# MSU-avionics.net
KiCad netlist of a schematic drawn in EasyEDA Pro
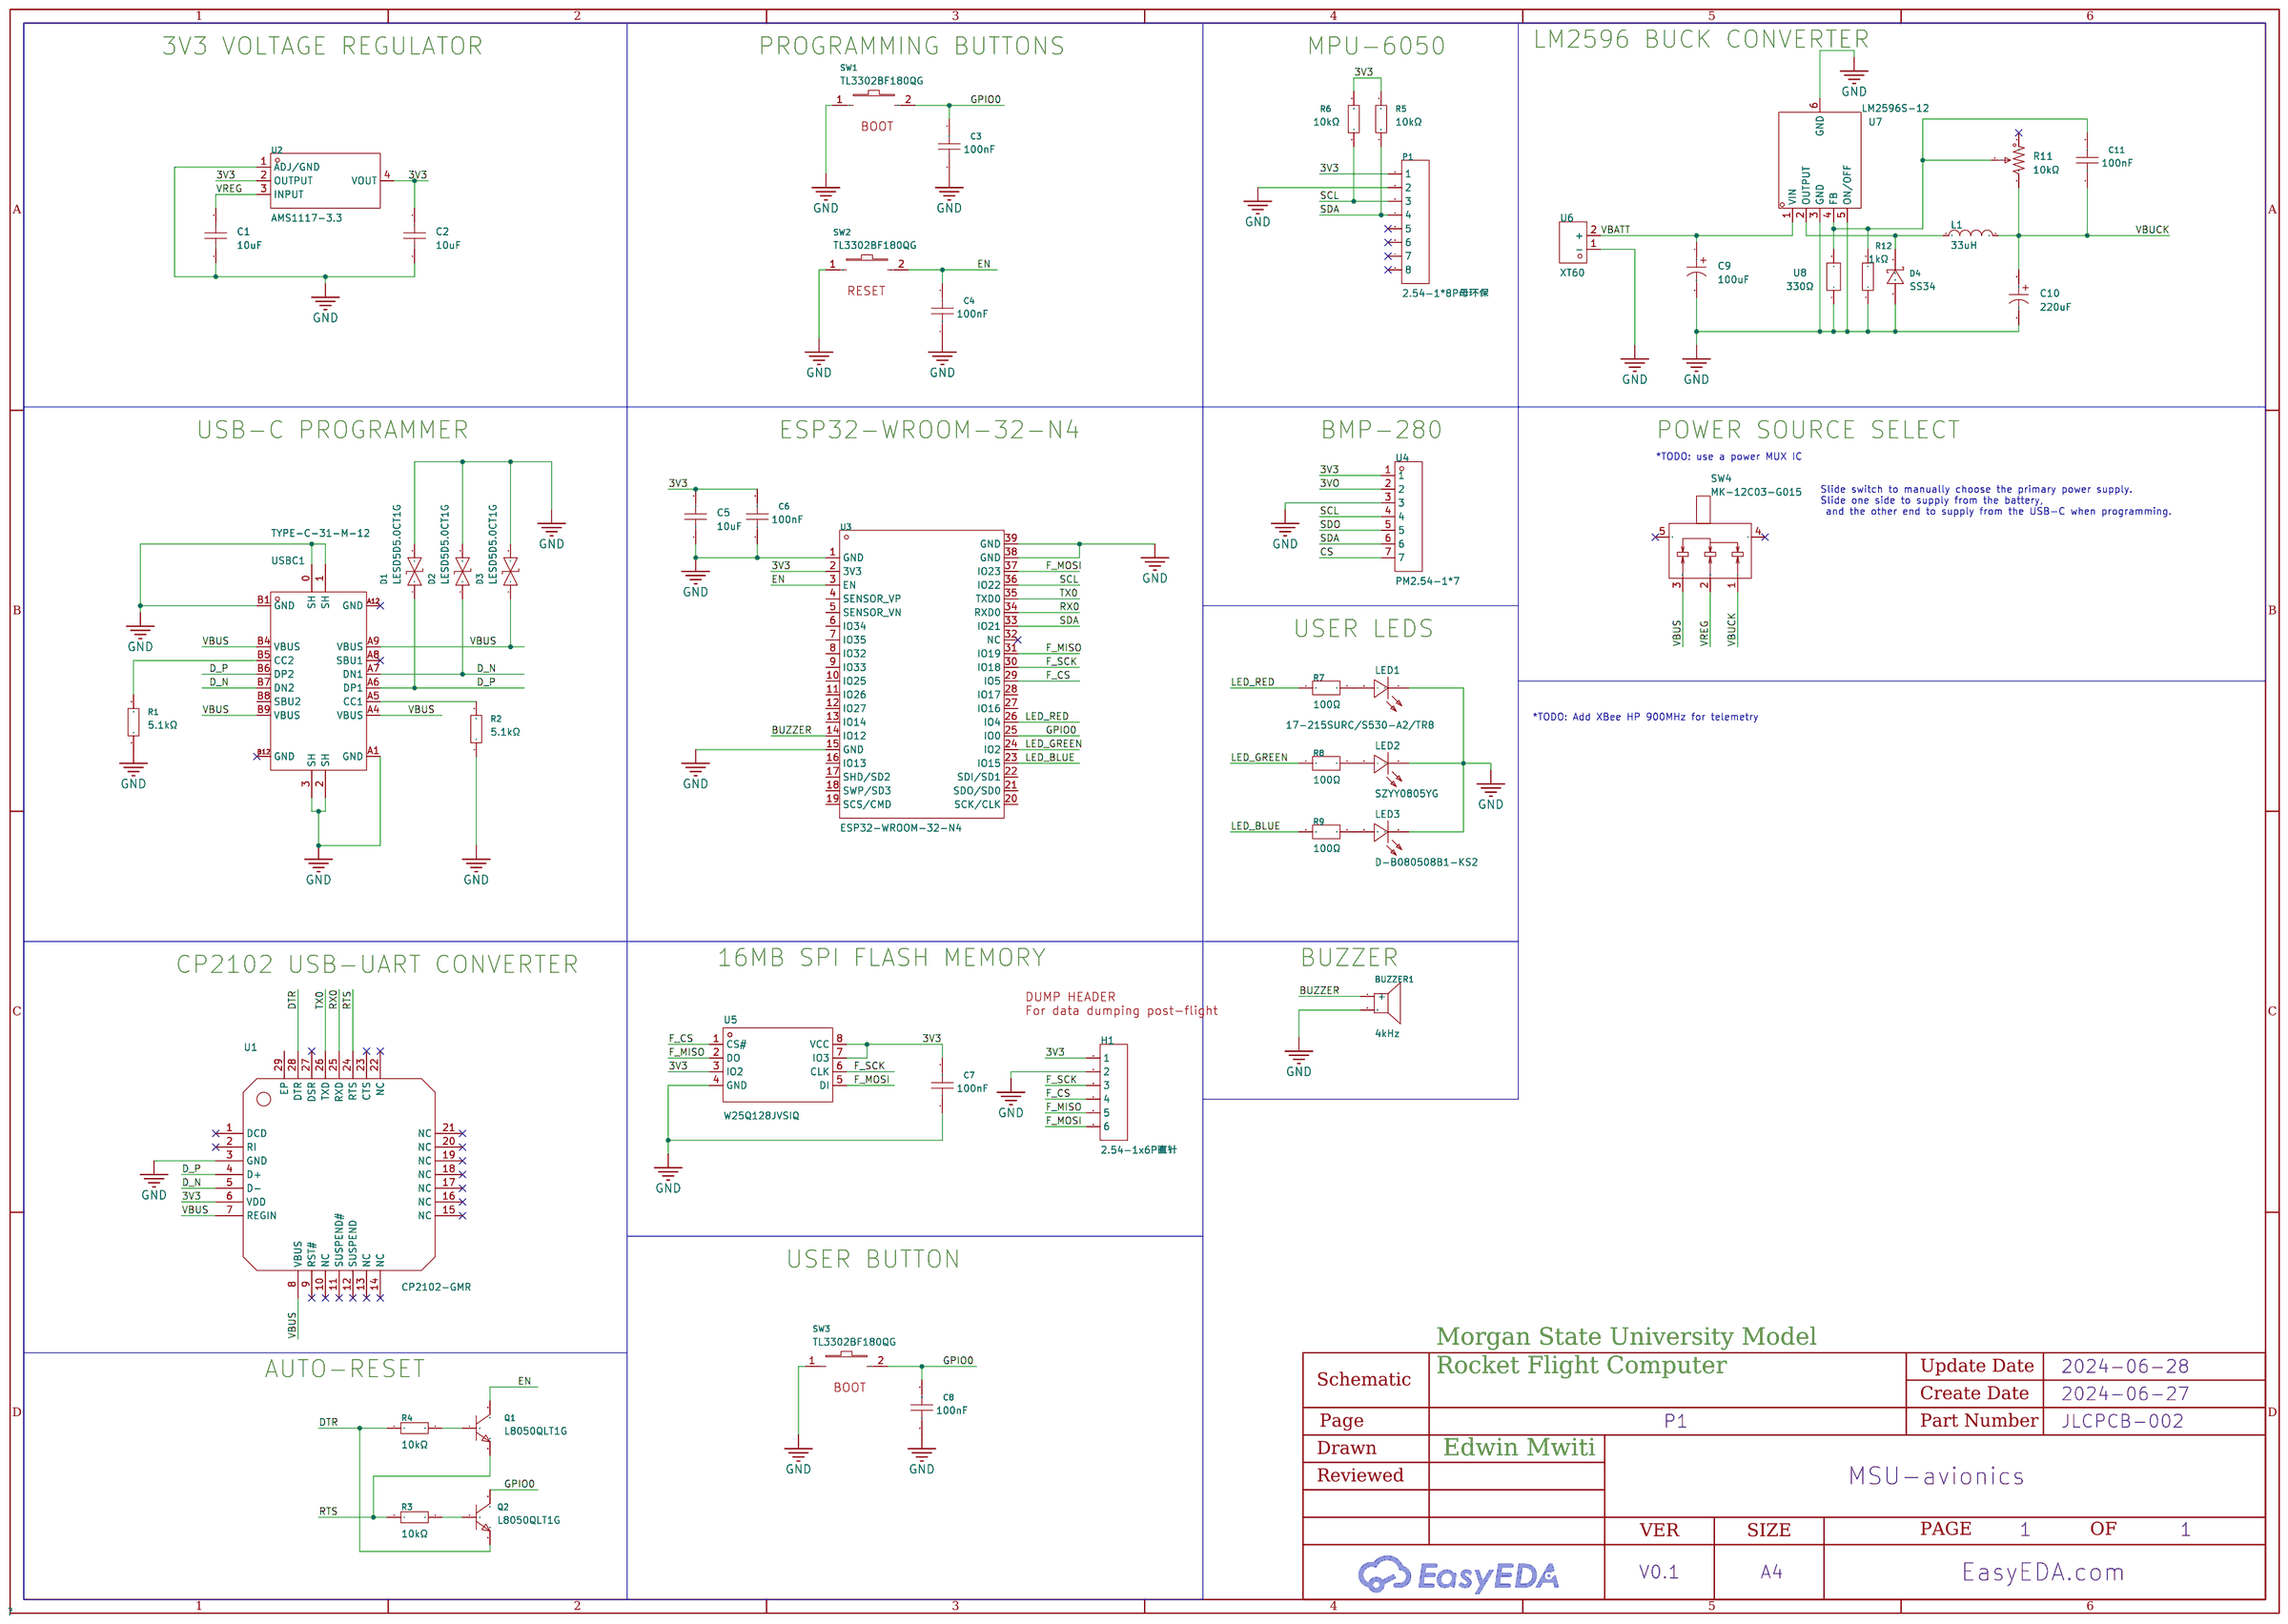
[diagram p0: schematic sheet]

(export (version "E")
  (design (tool "Eeschema 10.0.6"))
  (components
    (comp (ref "BUZZER1")
      (value "4kHz")
      (footprint "easyedapro:BUZ-TH_BD14.0-P5.00-D0.7-FD")
      (fields (field (name "Manufacturer Part") "PS1440P02BT") (field (name "Manufacturer") "TDK"))
      (libsource (lib "easyedapro") (part "PS1440P02BT"))
    )
    (comp (ref "C1")
      (value "10uF")
      (footprint "easyedapro:C0805")
      (fields
        (field (name "Manufacturer Part") "C0805X6S106K250NT")
        (field (name "Manufacturer") "SANYEAR(叁叶源)")
      )
      (libsource (lib "easyedapro") (part "C0805X6S106K250NT"))
    )
    (comp (ref "C2")
      (value "10uF")
      (footprint "easyedapro:C0805")
      (fields
        (field (name "Manufacturer Part") "C0805X6S106K250NT")
        (field (name "Manufacturer") "SANYEAR(叁叶源)")
      )
      (libsource (lib "easyedapro") (part "C0805X6S106K250NT"))
    )
    (comp (ref "C3")
      (value "100nF")
      (footprint "easyedapro:C0805")
      (fields
        (field (name "Manufacturer Part") "CT41G-0805-2X1-50V-0.1μF-K(N)")
        (field (name "Manufacturer") "TORCH(火炬)")
      )
      (libsource (lib "easyedapro") (part "CT41G-0805-2X1-50V-0.1UF-K(N)"))
    )
    (comp (ref "C4")
      (value "100nF")
      (footprint "easyedapro:C0805")
      (fields
        (field (name "Manufacturer Part") "CT41G-0805-2X1-50V-0.1μF-K(N)")
        (field (name "Manufacturer") "TORCH(火炬)")
      )
      (libsource (lib "easyedapro") (part "CT41G-0805-2X1-50V-0.1UF-K(N)"))
    )
    (comp (ref "C5")
      (value "10uF")
      (footprint "easyedapro:C0805")
      (fields
        (field (name "Manufacturer Part") "C0805X6S106K250NT")
        (field (name "Manufacturer") "SANYEAR(叁叶源)")
      )
      (libsource (lib "easyedapro") (part "C0805X6S106K250NT"))
    )
    (comp (ref "C6")
      (value "100nF")
      (footprint "easyedapro:C0805")
      (fields
        (field (name "Manufacturer Part") "CT41G-0805-2X1-50V-0.1μF-K(N)")
        (field (name "Manufacturer") "TORCH(火炬)")
      )
      (libsource (lib "easyedapro") (part "CT41G-0805-2X1-50V-0.1UF-K(N)"))
    )
    (comp (ref "C7")
      (value "100nF")
      (footprint "easyedapro:C0805")
      (fields
        (field (name "Manufacturer Part") "CT41G-0805-2X1-50V-0.1μF-K(N)")
        (field (name "Manufacturer") "TORCH(火炬)")
      )
      (libsource (lib "easyedapro") (part "CT41G-0805-2X1-50V-0.1UF-K(N)"))
    )
    (comp (ref "C8")
      (value "100nF")
      (footprint "easyedapro:C0805")
      (fields
        (field (name "Manufacturer Part") "CT41G-0805-2X1-50V-0.1μF-K(N)")
        (field (name "Manufacturer") "TORCH(火炬)")
      )
      (libsource (lib "easyedapro") (part "CT41G-0805-2X1-50V-0.1UF-K(N)"))
    )
    (comp (ref "C9")
      (value "100uF")
      (footprint "easyedapro:CAP-SMD_BD6.3-L6.6-W6.6-LS7.2-FD")
      (fields
        (field (name "Manufacturer Part") "RX100UF50V90RV0105")
        (field (name "Manufacturer") "KNSCHA(科尼盛)")
      )
      (libsource (lib "easyedapro") (part "RX100UF50V90RV0105"))
    )
    (comp (ref "C10")
      (value "220uF")
      (footprint "easyedapro:CAP-SMD_BD10.0-L10.3-W10.3-FD")
      (fields
        (field (name "Manufacturer Part") "FZ220UF50V90RV0126")
        (field (name "Manufacturer") "KNSCHA(科尼盛)")
      )
      (libsource (lib "easyedapro") (part "FZ220UF50V90RV0126"))
    )
    (comp (ref "C11")
      (value "100nF")
      (footprint "easyedapro:C0805")
      (fields
        (field (name "Manufacturer Part") "CT41G-0805-2X1-50V-0.1μF-K(N)")
        (field (name "Manufacturer") "TORCH(火炬)")
      )
      (libsource (lib "easyedapro") (part "CT41G-0805-2X1-50V-0.1UF-K(N)"))
    )
    (comp (ref "D1")
      (value "LESD5D5.0CT1G")
      (footprint "easyedapro:SOD-523_L1.2-W0.8-LS1.6-BI")
      (fields (field (name "Manufacturer") "LRC(乐山无线电)"))
      (libsource (lib "easyedapro") (part "LESD5D5.0CT1G"))
    )
    (comp (ref "D2")
      (value "LESD5D5.0CT1G")
      (footprint "easyedapro:SOD-523_L1.2-W0.8-LS1.6-BI")
      (fields (field (name "Manufacturer") "LRC(乐山无线电)"))
      (libsource (lib "easyedapro") (part "LESD5D5.0CT1G"))
    )
    (comp (ref "D3")
      (value "LESD5D5.0CT1G")
      (footprint "easyedapro:SOD-523_L1.2-W0.8-LS1.6-BI")
      (fields (field (name "Manufacturer") "LRC(乐山无线电)"))
      (libsource (lib "easyedapro") (part "LESD5D5.0CT1G"))
    )
    (comp (ref "D4")
      (value "SS34")
      (footprint "easyedapro:SMA_L4.4-W2.6-LS5.0-RD")
      (description "Forward Voltage (Vf@If):550mV@3A Reverse Voltage (Vr):40V Average Rectified Current (Io):3A")
      (fields (field (name "Manufacturer") "High Diode(海德)"))
      (libsource (lib "easyedapro") (part "SS34_C466502"))
    )
    (comp (ref "H1")
      (value "2.54-1x6P直针")
      (footprint "easyedapro:HDR-TH_6P-P2.54-V-M-1")
      (fields (field (name "Manufacturer") "BOOMELE(博穆精密)"))
      (libsource (lib "easyedapro") (part "Header-Male-2.54_1x6"))
    )
    (comp (ref "L1")
      (value "33uH")
      (footprint "easyedapro:IND-SMD_L12.3-W12.3")
      (fields (field (name "Manufacturer Part") "CYH127-33UH") (field (name "Manufacturer") "SHOU HAN(首韩)"))
      (libsource (lib "easyedapro") (part "CYH127-33UH"))
    )
    (comp (ref "LED1")
      (value "17-215SURC/S530-A2/TR8")
      (footprint "easyedapro:LED0805-RD_RED")
      (description "Emitted Color:Red")
      (fields (field (name "Manufacturer") "EVERLIGHT(亿光)"))
      (libsource (lib "easyedapro") (part "17-215SURC/S530-A2/TR8(TY)"))
    )
    (comp (ref "LED2")
      (value "SZYY0805YG")
      (footprint "easyedapro:LED0805-R-RD_GREEN")
      (description "Emitted Color:Green-yellow")
      (fields (field (name "Manufacturer") "yongyu(永裕光电)"))
      (libsource (lib "easyedapro") (part "SZYY0805YG"))
    )
    (comp (ref "LED3")
      (value "D-B080508B1-KS2")
      (footprint "easyedapro:LED0805-RD")
      (description "Emitted Color:Blue")
      (fields (field (name "Manufacturer") "ARKLED(方舟)"))
      (libsource (lib "easyedapro") (part "D-B080508B1-KS2"))
    )
    (comp (ref "P1")
      (value "2.54-1*8P母环保")
      (footprint "easyedapro:HDR-TH_8P-P2.54-V-F-1")
      (fields (field (name "Manufacturer") "BOOMELE(博穆精密)"))
      (libsource (lib "easyedapro") (part "Header-Female-2.54_1x8"))
    )
    (comp (ref "Q1")
      (value "L8050QLT1G")
      (footprint "easyedapro:SOT-23-3_L2.9-W1.3-P1.90-LS2.4-BR")
      (fields (field (name "Manufacturer") "LRC(乐山无线电)"))
      (libsource (lib "easyedapro") (part "L8050QLT1G"))
    )
    (comp (ref "Q2")
      (value "L8050QLT1G")
      (footprint "easyedapro:SOT-23-3_L2.9-W1.3-P1.90-LS2.4-BR")
      (fields (field (name "Manufacturer") "LRC(乐山无线电)"))
      (libsource (lib "easyedapro") (part "L8050QLT1G"))
    )
    (comp (ref "R1")
      (value "5.1kΩ")
      (footprint "easyedapro:R0805")
      (fields (field (name "Manufacturer Part") "RMC08055.1K1%N") (field (name "Manufacturer") "Tyohm(幸亚电阻)"))
      (libsource (lib "easyedapro") (part "RMC08055.1K1%N"))
    )
    (comp (ref "R2")
      (value "5.1kΩ")
      (footprint "easyedapro:R0805")
      (fields (field (name "Manufacturer Part") "RMC08055.1K1%N") (field (name "Manufacturer") "Tyohm(幸亚电阻)"))
      (libsource (lib "easyedapro") (part "RMC08055.1K1%N"))
    )
    (comp (ref "R3")
      (value "10kΩ")
      (footprint "easyedapro:R0805")
      (fields (field (name "Manufacturer Part") "RMC080510K1%N") (field (name "Manufacturer") "Tyohm(幸亚电阻)"))
      (libsource (lib "easyedapro") (part "RMC080510K1%N"))
    )
    (comp (ref "R4")
      (value "10kΩ")
      (footprint "easyedapro:R0805")
      (fields (field (name "Manufacturer Part") "RMC080510K1%N") (field (name "Manufacturer") "Tyohm(幸亚电阻)"))
      (libsource (lib "easyedapro") (part "RMC080510K1%N"))
    )
    (comp (ref "R5")
      (value "10kΩ")
      (footprint "easyedapro:R0805")
      (fields (field (name "Manufacturer Part") "RMC080510K1%N") (field (name "Manufacturer") "Tyohm(幸亚电阻)"))
      (libsource (lib "easyedapro") (part "RMC080510K1%N"))
    )
    (comp (ref "R6")
      (value "10kΩ")
      (footprint "easyedapro:R0805")
      (fields (field (name "Manufacturer Part") "RMC080510K1%N") (field (name "Manufacturer") "Tyohm(幸亚电阻)"))
      (libsource (lib "easyedapro") (part "RMC080510K1%N"))
    )
    (comp (ref "R7")
      (value "100Ω")
      (footprint "easyedapro:R0603")
      (fields
        (field (name "Manufacturer Part") "TNPW0603100RBEEA")
        (field (name "Manufacturer") "VISHAY(威世)")
      )
      (libsource (lib "easyedapro") (part "TNPW0603100RBEEA"))
    )
    (comp (ref "R8")
      (value "100Ω")
      (footprint "easyedapro:R0603")
      (fields
        (field (name "Manufacturer Part") "TNPW0603100RBEEA")
        (field (name "Manufacturer") "VISHAY(威世)")
      )
      (libsource (lib "easyedapro") (part "TNPW0603100RBEEA"))
    )
    (comp (ref "R9")
      (value "100Ω")
      (footprint "easyedapro:R0603")
      (fields
        (field (name "Manufacturer Part") "TNPW0603100RBEEA")
        (field (name "Manufacturer") "VISHAY(威世)")
      )
      (libsource (lib "easyedapro") (part "TNPW0603100RBEEA"))
    )
    (comp (ref "R11")
      (value "10kΩ")
      (footprint "easyedapro:RES-ADJ-TH_3362P")
      (description "Resistance: Tolerance:±10% Tolerance:±10%")
      (fields (field (name "Manufacturer Part") "3362P-1-103") (field (name "Manufacturer") "BOCHEN(博晨)"))
      (libsource (lib "easyedapro") (part "3362P-1-103_C118956"))
    )
    (comp (ref "R12")
      (value "1kΩ")
      (footprint "easyedapro:R0805")
      (fields (field (name "Manufacturer Part") "RMC08051K5%N") (field (name "Manufacturer") "Tyohm(幸亚电阻)"))
      (libsource (lib "easyedapro") (part "RMC08051K5%N"))
    )
    (comp (ref "SW1")
      (value "TL3302BF180QG")
      (footprint "easyedapro:SW-SMD_L6.0-W3.5-LS10.2")
      (fields (field (name "Manufacturer") "E-Switch"))
      (libsource (lib "easyedapro") (part "TL3302BF180QG"))
    )
    (comp (ref "SW2")
      (value "TL3302BF180QG")
      (footprint "easyedapro:SW-SMD_L6.0-W3.5-LS10.2")
      (fields (field (name "Manufacturer") "E-Switch"))
      (libsource (lib "easyedapro") (part "TL3302BF180QG"))
    )
    (comp (ref "SW3")
      (value "TL3302BF180QG")
      (footprint "easyedapro:SW-SMD_L6.0-W3.5-LS10.2")
      (fields (field (name "Manufacturer") "E-Switch"))
      (libsource (lib "easyedapro") (part "TL3302BF180QG"))
    )
    (comp (ref "SW4")
      (value "MK-12C03-G015")
      (footprint "easyedapro:SW-SMD_MK-12C03-G015")
      (fields (field (name "Manufacturer") "G-Switch(品赞)"))
      (libsource (lib "easyedapro") (part "MK-12C03-G015"))
    )
    (comp (ref "U1")
      (value "CP2102-GMR")
      (footprint "easyedapro:WQFN-28_L5.0-W5.0-P0.50-BL-EP3.2")
      (fields (field (name "Manufacturer") "SKYWORKS/SILICON LABS(芯科)"))
      (libsource (lib "easyedapro") (part "CP2102-GMR"))
    )
    (comp (ref "U2")
      (value "AMS1117-3.3")
      (footprint "easyedapro:SOT-223-3_L6.5-W3.4-P2.30-LS7.0-BR")
      (fields (field (name "Manufacturer") "TECH PUBLIC(台舟)"))
      (libsource (lib "easyedapro") (part "AMS1117-3.3_C18212698"))
    )
    (comp (ref "U3")
      (value "ESP32-WROOM-32-N4")
      (footprint "easyedapro:WIFIM-SMD_ESP32-WROOM-32-N4")
      (fields (field (name "Manufacturer") "ESPRESSIF(乐鑫)"))
      (libsource (lib "easyedapro") (part "ESP32-WROOM-32"))
    )
    (comp (ref "U4")
      (value "PM2.54-1*7")
      (footprint "easyedapro:HDR-TH_7P-P2.54-V-F")
      (description "Holes Structure:1x7P Pitch:2.54mm Number of Rows:Plugin Contact Plating:Gold")
      (fields (field (name "Manufacturer") "ZHOURI(洲日)"))
      (libsource (lib "easyedapro") (part "PM2.54-1*7"))
    )
    (comp (ref "U5")
      (value "W25Q128JVSIQ")
      (footprint "easyedapro:SOIC-8_L5.3-W5.3-P1.27-LS8.0-BL")
      (fields (field (name "Manufacturer") "WINBOND(华邦)"))
      (libsource (lib "easyedapro") (part "W25Q128JVSIQTR"))
    )
    (comp (ref "U6")
      (value "XT60")
      (footprint "easyedapro:CONN-TH_XT60")
      (fields (field (name "Manufacturer") "AMASS(艾迈斯)"))
      (libsource (lib "easyedapro") (part "XT60"))
    )
    (comp (ref "U7")
      (value "LM2596S-12")
      (footprint "easyedapro:TO-263-5_L10.2-W8.9-P1.70-LS15.0-BR")
      (fields (field (name "Manufacturer") "HXY MOSFET(华轩阳电子)"))
      (libsource (lib "easyedapro") (part "LM2596S-12_C5349986"))
    )
    (comp (ref "U8")
      (value "330Ω")
      (footprint "easyedapro:R0805")
      (fields
        (field (name "Manufacturer Part") "CRCW0805330RFKEAHP")
        (field (name "Manufacturer") "VISHAY(威世)")
      )
      (libsource (lib "easyedapro") (part "CRCW0805330RFKEAHP"))
    )
    (comp (ref "USBC1")
      (value "TYPE-C-31-M-12")
      (footprint "easyedapro:USB-C_SMD-TYPE-C-31-M-12")
      (fields (field (name "Manufacturer") "韩国韩荣"))
      (libsource (lib "easyedapro") (part "TYPE-C-31-M-12"))
    )
  )
  (nets
    (net (code "1") (name "/3V3") (class "Default")
      (node (ref "C2") (pin "2") (pinfunction "2_2") (pintype "input"))
      (node (ref "C5") (pin "2") (pinfunction "2_2") (pintype "input"))
      (node (ref "C6") (pin "2") (pinfunction "2_2") (pintype "input"))
      (node (ref "C7") (pin "2") (pinfunction "2_2") (pintype "input"))
      (node (ref "H1") (pin "1") (pinfunction "1_1") (pintype "input"))
      (node (ref "P1") (pin "1") (pinfunction "1_1") (pintype "input"))
      (node (ref "R5") (pin "2") (pinfunction "2_2") (pintype "input"))
      (node (ref "R6") (pin "2") (pinfunction "2_2") (pintype "input"))
      (node (ref "U1") (pin "6") (pinfunction "VDD_6") (pintype "unspecified"))
      (node (ref "U2") (pin "2") (pinfunction "OUTPUT_2") (pintype "input"))
      (node (ref "U2") (pin "4") (pinfunction "VOUT_4") (pintype "input"))
      (node (ref "U3") (pin "2") (pinfunction "3V3_2") (pintype "input"))
      (node (ref "U4") (pin "1") (pinfunction "1_1") (pintype "unspecified"))
      (node (ref "U5") (pin "3") (pinfunction "IO2_3") (pintype "unspecified"))
      (node (ref "U5") (pin "7") (pinfunction "IO3_7") (pintype "unspecified"))
      (node (ref "U5") (pin "8") (pinfunction "VCC_8") (pintype "unspecified"))
    )
    (net (code "2") (name "/3VO") (class "Default")
      (node (ref "U4") (pin "2") (pinfunction "2_2") (pintype "unspecified"))
    )
    (net (code "3") (name "/BUZZER") (class "Default")
      (node (ref "BUZZER1") (pin "1") (pinfunction "+_1") (pintype "input"))
      (node (ref "U3") (pin "14") (pinfunction "IO12_14") (pintype "input"))
    )
    (net (code "4") (name "/CS") (class "Default")
      (node (ref "U4") (pin "7") (pinfunction "7_7") (pintype "unspecified"))
    )
    (net (code "5") (name "/DTR") (class "Default")
      (node (ref "Q2") (pin "2") (pinfunction "E_2") (pintype "input"))
      (node (ref "R4") (pin "1") (pinfunction "1_1") (pintype "input"))
      (node (ref "U1") (pin "28") (pinfunction "DTR_28") (pintype "unspecified"))
    )
    (net (code "6") (name "/D_N") (class "Default")
      (node (ref "D2") (pin "1") (pinfunction "1_1") (pintype "input"))
      (node (ref "U1") (pin "5") (pinfunction "D-_5") (pintype "unspecified"))
      (node (ref "USBC1") (pin "A7") (pinfunction "DN1_A7") (pintype "unspecified"))
      (node (ref "USBC1") (pin "B7") (pinfunction "DN2_B7") (pintype "unspecified"))
    )
    (net (code "7") (name "/D_P") (class "Default")
      (node (ref "D1") (pin "1") (pinfunction "1_1") (pintype "input"))
      (node (ref "U1") (pin "4") (pinfunction "D+_4") (pintype "unspecified"))
      (node (ref "USBC1") (pin "A6") (pinfunction "DP1_A6") (pintype "unspecified"))
      (node (ref "USBC1") (pin "B6") (pinfunction "DP2_B6") (pintype "unspecified"))
    )
    (net (code "8") (name "/EN") (class "Default")
      (node (ref "C4") (pin "2") (pinfunction "2_2") (pintype "input"))
      (node (ref "Q1") (pin "3") (pinfunction "C_3") (pintype "input"))
      (node (ref "SW2") (pin "2") (pinfunction "2_2") (pintype "input"))
      (node (ref "U3") (pin "3") (pinfunction "EN_3") (pintype "input"))
    )
    (net (code "9") (name "/F_CS") (class "Default")
      (node (ref "H1") (pin "4") (pinfunction "4_4") (pintype "input"))
      (node (ref "U3") (pin "29") (pinfunction "IO5_29") (pintype "input"))
      (node (ref "U5") (pin "1") (pinfunction "CS#_1") (pintype "unspecified"))
    )
    (net (code "10") (name "/F_MISO") (class "Default")
      (node (ref "H1") (pin "5") (pinfunction "5_5") (pintype "input"))
      (node (ref "U3") (pin "31") (pinfunction "IO19_31") (pintype "input"))
      (node (ref "U5") (pin "2") (pinfunction "DO_2") (pintype "unspecified"))
    )
    (net (code "11") (name "/F_MOSI") (class "Default")
      (node (ref "H1") (pin "6") (pinfunction "6_6") (pintype "input"))
      (node (ref "U3") (pin "37") (pinfunction "IO23_37") (pintype "input"))
      (node (ref "U5") (pin "5") (pinfunction "DI_5") (pintype "unspecified"))
    )
    (net (code "12") (name "/F_SCK") (class "Default")
      (node (ref "H1") (pin "3") (pinfunction "3_3") (pintype "input"))
      (node (ref "U3") (pin "30") (pinfunction "IO18_30") (pintype "input"))
      (node (ref "U5") (pin "6") (pinfunction "CLK_6") (pintype "unspecified"))
    )
    (net (code "13") (name "/GPIO0") (class "Default")
      (node (ref "C3") (pin "2") (pinfunction "2_2") (pintype "input"))
      (node (ref "C8") (pin "2") (pinfunction "2_2") (pintype "input"))
      (node (ref "Q2") (pin "3") (pinfunction "C_3") (pintype "input"))
      (node (ref "SW1") (pin "2") (pinfunction "2_2") (pintype "input"))
      (node (ref "SW3") (pin "2") (pinfunction "2_2") (pintype "input"))
      (node (ref "U3") (pin "25") (pinfunction "IO0_25") (pintype "input"))
    )
    (net (code "14") (name "/LED_BLUE") (class "Default")
      (node (ref "R9") (pin "1") (pinfunction "1_1") (pintype "input"))
      (node (ref "U3") (pin "23") (pinfunction "IO15_23") (pintype "input"))
    )
    (net (code "15") (name "/LED_GREEN") (class "Default")
      (node (ref "R8") (pin "1") (pinfunction "1_1") (pintype "input"))
      (node (ref "U3") (pin "24") (pinfunction "IO2_24") (pintype "input"))
    )
    (net (code "16") (name "/LED_RED") (class "Default")
      (node (ref "R7") (pin "1") (pinfunction "1_1") (pintype "input"))
      (node (ref "U3") (pin "26") (pinfunction "IO4_26") (pintype "input"))
    )
    (net (code "17") (name "/RTS") (class "Default")
      (node (ref "Q1") (pin "2") (pinfunction "E_2") (pintype "input"))
      (node (ref "R3") (pin "1") (pinfunction "1_1") (pintype "input"))
      (node (ref "U1") (pin "24") (pinfunction "RTS_24") (pintype "unspecified"))
    )
    (net (code "18") (name "/RX0") (class "Default")
      (node (ref "U1") (pin "25") (pinfunction "RXD_25") (pintype "unspecified"))
      (node (ref "U3") (pin "34") (pinfunction "RXD0_34") (pintype "input"))
    )
    (net (code "19") (name "/SCL") (class "Default")
      (node (ref "P1") (pin "3") (pinfunction "3_3") (pintype "input"))
      (node (ref "R6") (pin "1") (pinfunction "1_1") (pintype "input"))
      (node (ref "U3") (pin "36") (pinfunction "IO22_36") (pintype "input"))
      (node (ref "U4") (pin "4") (pinfunction "4_4") (pintype "unspecified"))
    )
    (net (code "20") (name "/SDA") (class "Default")
      (node (ref "P1") (pin "4") (pinfunction "4_4") (pintype "input"))
      (node (ref "R5") (pin "1") (pinfunction "1_1") (pintype "input"))
      (node (ref "U3") (pin "33") (pinfunction "IO21_33") (pintype "input"))
      (node (ref "U4") (pin "6") (pinfunction "6_6") (pintype "unspecified"))
    )
    (net (code "21") (name "/SDO") (class "Default")
      (node (ref "U4") (pin "5") (pinfunction "5_5") (pintype "unspecified"))
    )
    (net (code "22") (name "/TX0") (class "Default")
      (node (ref "U1") (pin "26") (pinfunction "TXD_26") (pintype "unspecified"))
      (node (ref "U3") (pin "35") (pinfunction "TXD0_35") (pintype "input"))
    )
    (net (code "23") (name "/VBATT") (class "Default")
      (node (ref "C9") (pin "1") (pinfunction "1_1") (pintype "input"))
      (node (ref "U6") (pin "2") (pinfunction "+_2") (pintype "input"))
      (node (ref "U7") (pin "1") (pinfunction "VIN_1") (pintype "unspecified"))
    )
    (net (code "24") (name "/VBUCK") (class "Default")
      (node (ref "C10") (pin "1") (pinfunction "1_1") (pintype "input"))
      (node (ref "C11") (pin "1") (pinfunction "1_1") (pintype "input"))
      (node (ref "L1") (pin "2") (pinfunction "2_2") (pintype "unspecified"))
      (node (ref "R11") (pin "3") (pinfunction "3_3") (pintype "unspecified"))
      (node (ref "SW4") (pin "1") (pinfunction "1_1") (pintype "unspecified"))
    )
    (net (code "25") (name "/VBUS") (class "Default")
      (node (ref "D3") (pin "1") (pinfunction "1_1") (pintype "input"))
      (node (ref "SW4") (pin "3") (pinfunction "3_3") (pintype "unspecified"))
      (node (ref "U1") (pin "7") (pinfunction "REGIN_7") (pintype "unspecified"))
      (node (ref "U1") (pin "8") (pinfunction "VBUS_8") (pintype "unspecified"))
      (node (ref "USBC1") (pin "A4") (pinfunction "VBUS_A4") (pintype "unspecified"))
      (node (ref "USBC1") (pin "A9") (pinfunction "VBUS_A9") (pintype "unspecified"))
      (node (ref "USBC1") (pin "B4") (pinfunction "VBUS_B4") (pintype "unspecified"))
      (node (ref "USBC1") (pin "B9") (pinfunction "VBUS_B9") (pintype "unspecified"))
    )
    (net (code "26") (name "/VREG") (class "Default")
      (node (ref "C1") (pin "2") (pinfunction "2_2") (pintype "input"))
      (node (ref "SW4") (pin "2") (pinfunction "2_2") (pintype "unspecified"))
      (node (ref "U2") (pin "3") (pinfunction "INPUT_3") (pintype "input"))
    )
    (net (code "27") (name "GND") (class "Default")
      (node (ref "BUZZER1") (pin "2") (pinfunction "2_2") (pintype "input"))
      (node (ref "C1") (pin "1") (pinfunction "1_1") (pintype "input"))
      (node (ref "C10") (pin "2") (pinfunction "2_2") (pintype "input"))
      (node (ref "C2") (pin "1") (pinfunction "1_1") (pintype "input"))
      (node (ref "C3") (pin "1") (pinfunction "1_1") (pintype "input"))
      (node (ref "C4") (pin "1") (pinfunction "1_1") (pintype "input"))
      (node (ref "C5") (pin "1") (pinfunction "1_1") (pintype "input"))
      (node (ref "C6") (pin "1") (pinfunction "1_1") (pintype "input"))
      (node (ref "C7") (pin "1") (pinfunction "1_1") (pintype "input"))
      (node (ref "C8") (pin "1") (pinfunction "1_1") (pintype "input"))
      (node (ref "C9") (pin "2") (pinfunction "2_2") (pintype "input"))
      (node (ref "D1") (pin "2") (pinfunction "2_2") (pintype "input"))
      (node (ref "D2") (pin "2") (pinfunction "2_2") (pintype "input"))
      (node (ref "D3") (pin "2") (pinfunction "2_2") (pintype "input"))
      (node (ref "D4") (pin "2") (pinfunction "2_2") (pintype "input"))
      (node (ref "H1") (pin "2") (pinfunction "2_2") (pintype "input"))
      (node (ref "LED1") (pin "1") (pinfunction "K_1") (pintype "unspecified"))
      (node (ref "LED2") (pin "2") (pinfunction "-_2") (pintype "unspecified"))
      (node (ref "LED3") (pin "1") (pinfunction "K_1") (pintype "unspecified"))
      (node (ref "P1") (pin "2") (pinfunction "2_2") (pintype "input"))
      (node (ref "R1") (pin "1") (pinfunction "1_1") (pintype "input"))
      (node (ref "R12") (pin "1") (pinfunction "1_1") (pintype "input"))
      (node (ref "R2") (pin "1") (pinfunction "1_1") (pintype "input"))
      (node (ref "SW1") (pin "1") (pinfunction "1_1") (pintype "input"))
      (node (ref "SW2") (pin "1") (pinfunction "1_1") (pintype "input"))
      (node (ref "SW3") (pin "1") (pinfunction "1_1") (pintype "input"))
      (node (ref "U1") (pin "3") (pinfunction "GND_3") (pintype "unspecified"))
      (node (ref "U2") (pin "1") (pinfunction "ADJ/GND_1") (pintype "input"))
      (node (ref "U3") (pin "1") (pinfunction "GND_1") (pintype "input"))
      (node (ref "U3") (pin "15") (pinfunction "GND_15") (pintype "input"))
      (node (ref "U3") (pin "38") (pinfunction "GND_38") (pintype "input"))
      (node (ref "U3") (pin "39") (pinfunction "GND_39") (pintype "input"))
      (node (ref "U4") (pin "3") (pinfunction "3_3") (pintype "unspecified"))
      (node (ref "U5") (pin "4") (pinfunction "GND_4") (pintype "unspecified"))
      (node (ref "U6") (pin "1") (pinfunction "-_1") (pintype "input"))
      (node (ref "U7") (pin "3") (pinfunction "GND_3") (pintype "unspecified"))
      (node (ref "U7") (pin "5") (pinfunction "ON/OFF_5") (pintype "unspecified"))
      (node (ref "U7") (pin "6") (pinfunction "GND_6") (pintype "unspecified"))
      (node (ref "U8") (pin "1") (pinfunction "1_1") (pintype "unspecified"))
      (node (ref "USBC1") (pin "0") (pinfunction "SH_0") (pintype "unspecified"))
      (node (ref "USBC1") (pin "1") (pinfunction "SH_1") (pintype "unspecified"))
      (node (ref "USBC1") (pin "2") (pinfunction "SH_2") (pintype "unspecified"))
      (node (ref "USBC1") (pin "3") (pinfunction "SH_3") (pintype "unspecified"))
      (node (ref "USBC1") (pin "A1") (pinfunction "GND_A1") (pintype "unspecified"))
      (node (ref "USBC1") (pin "B1") (pinfunction "GND_B1") (pintype "unspecified"))
    )
    (net (code "28") (name "Net-(LED1-A)") (class "Default")
      (node (ref "LED1") (pin "2") (pinfunction "A_2") (pintype "unspecified"))
      (node (ref "R7") (pin "2") (pinfunction "2_2") (pintype "input"))
    )
    (net (code "29") (name "Net-(LED2-+)") (class "Default")
      (node (ref "LED2") (pin "1") (pinfunction "+_1") (pintype "unspecified"))
      (node (ref "R8") (pin "2") (pinfunction "2_2") (pintype "input"))
    )
    (net (code "30") (name "Net-(LED3-A)") (class "Default")
      (node (ref "LED3") (pin "2") (pinfunction "A_2") (pintype "unspecified"))
      (node (ref "R9") (pin "2") (pinfunction "2_2") (pintype "input"))
    )
    (net (code "31") (name "Net-(Q1-B)") (class "Default")
      (node (ref "Q1") (pin "1") (pinfunction "B_1") (pintype "input"))
      (node (ref "R4") (pin "2") (pinfunction "2_2") (pintype "input"))
    )
    (net (code "32") (name "Net-(Q2-B)") (class "Default")
      (node (ref "Q2") (pin "1") (pinfunction "B_1") (pintype "input"))
      (node (ref "R3") (pin "2") (pinfunction "2_2") (pintype "input"))
    )
    (net (code "33") (name "Net-(U7-FB)") (class "Default")
      (node (ref "C11") (pin "2") (pinfunction "2_2") (pintype "input"))
      (node (ref "R11") (pin "2") (pinfunction "2_2") (pintype "unspecified"))
      (node (ref "R12") (pin "2") (pinfunction "2_2") (pintype "input"))
      (node (ref "U7") (pin "4") (pinfunction "FB_4") (pintype "unspecified"))
      (node (ref "U8") (pin "2") (pinfunction "2_2") (pintype "unspecified"))
    )
    (net (code "34") (name "Net-(U7-OUTPUT)") (class "Default")
      (node (ref "D4") (pin "1") (pinfunction "1_1") (pintype "input"))
      (node (ref "L1") (pin "1") (pinfunction "1_1") (pintype "unspecified"))
      (node (ref "U7") (pin "2") (pinfunction "OUTPUT_2") (pintype "unspecified"))
    )
    (net (code "35") (name "Net-(USBC1-CC1)") (class "Default")
      (node (ref "R2") (pin "2") (pinfunction "2_2") (pintype "input"))
      (node (ref "USBC1") (pin "A5") (pinfunction "CC1_A5") (pintype "unspecified"))
    )
    (net (code "36") (name "Net-(USBC1-CC2)") (class "Default")
      (node (ref "R1") (pin "2") (pinfunction "2_2") (pintype "input"))
      (node (ref "USBC1") (pin "B5") (pinfunction "CC2_B5") (pintype "unspecified"))
    )
    (net (code "37") (name "unconnected-(P1-Pad5)") (class "Default")
      (node (ref "P1") (pin "5") (pinfunction "5_5") (pintype "input+no_connect"))
    )
    (net (code "38") (name "unconnected-(P1-Pad6)") (class "Default")
      (node (ref "P1") (pin "6") (pinfunction "6_6") (pintype "input+no_connect"))
    )
    (net (code "39") (name "unconnected-(P1-Pad7)") (class "Default")
      (node (ref "P1") (pin "7") (pinfunction "7_7") (pintype "input+no_connect"))
    )
    (net (code "40") (name "unconnected-(P1-Pad8)") (class "Default")
      (node (ref "P1") (pin "8") (pinfunction "8_8") (pintype "input+no_connect"))
    )
    (net (code "41") (name "unconnected-(R11-Pad1)") (class "Default")
      (node (ref "R11") (pin "1") (pinfunction "1_1") (pintype "unspecified+no_connect"))
    )
    (net (code "42") (name "unconnected-(SW4-Pad4)") (class "Default")
      (node (ref "SW4") (pin "4") (pinfunction "4_4") (pintype "unspecified+no_connect"))
    )
    (net (code "43") (name "unconnected-(SW4-Pad5)") (class "Default")
      (node (ref "SW4") (pin "5") (pinfunction "5_5") (pintype "unspecified+no_connect"))
    )
    (net (code "44") (name "unconnected-(U1-CTS-Pad23)") (class "Default")
      (node (ref "U1") (pin "23") (pinfunction "CTS_23") (pintype "unspecified+no_connect"))
    )
    (net (code "45") (name "unconnected-(U1-DCD-Pad1)") (class "Default")
      (node (ref "U1") (pin "1") (pinfunction "DCD_1") (pintype "unspecified+no_connect"))
    )
    (net (code "46") (name "unconnected-(U1-DSR-Pad27)") (class "Default")
      (node (ref "U1") (pin "27") (pinfunction "DSR_27") (pintype "unspecified+no_connect"))
    )
    (net (code "47") (name "unconnected-(U1-EP-Pad29)") (class "Default")
      (node (ref "U1") (pin "29") (pinfunction "EP_29") (pintype "unspecified"))
    )
    (net (code "48") (name "unconnected-(U1-NC-Pad10)") (class "Default")
      (node (ref "U1") (pin "10") (pinfunction "NC_10") (pintype "unspecified+no_connect"))
    )
    (net (code "49") (name "unconnected-(U1-NC-Pad13)") (class "Default")
      (node (ref "U1") (pin "13") (pinfunction "NC_13") (pintype "unspecified+no_connect"))
    )
    (net (code "50") (name "unconnected-(U1-NC-Pad14)") (class "Default")
      (node (ref "U1") (pin "14") (pinfunction "NC_14") (pintype "unspecified+no_connect"))
    )
    (net (code "51") (name "unconnected-(U1-NC-Pad15)") (class "Default")
      (node (ref "U1") (pin "15") (pinfunction "NC_15") (pintype "unspecified+no_connect"))
    )
    (net (code "52") (name "unconnected-(U1-NC-Pad16)") (class "Default")
      (node (ref "U1") (pin "16") (pinfunction "NC_16") (pintype "unspecified+no_connect"))
    )
    (net (code "53") (name "unconnected-(U1-NC-Pad17)") (class "Default")
      (node (ref "U1") (pin "17") (pinfunction "NC_17") (pintype "unspecified+no_connect"))
    )
    (net (code "54") (name "unconnected-(U1-NC-Pad18)") (class "Default")
      (node (ref "U1") (pin "18") (pinfunction "NC_18") (pintype "unspecified+no_connect"))
    )
    (net (code "55") (name "unconnected-(U1-NC-Pad19)") (class "Default")
      (node (ref "U1") (pin "19") (pinfunction "NC_19") (pintype "unspecified+no_connect"))
    )
    (net (code "56") (name "unconnected-(U1-NC-Pad20)") (class "Default")
      (node (ref "U1") (pin "20") (pinfunction "NC_20") (pintype "unspecified+no_connect"))
    )
    (net (code "57") (name "unconnected-(U1-NC-Pad21)") (class "Default")
      (node (ref "U1") (pin "21") (pinfunction "NC_21") (pintype "unspecified+no_connect"))
    )
    (net (code "58") (name "unconnected-(U1-NC-Pad22)") (class "Default")
      (node (ref "U1") (pin "22") (pinfunction "NC_22") (pintype "unspecified+no_connect"))
    )
    (net (code "59") (name "unconnected-(U1-RI-Pad2)") (class "Default")
      (node (ref "U1") (pin "2") (pinfunction "RI_2") (pintype "unspecified+no_connect"))
    )
    (net (code "60") (name "unconnected-(U1-RST#-Pad9)") (class "Default")
      (node (ref "U1") (pin "9") (pinfunction "RST#_9") (pintype "unspecified+no_connect"))
    )
    (net (code "61") (name "unconnected-(U1-SUSPEND#-Pad11)") (class "Default")
      (node (ref "U1") (pin "11") (pinfunction "SUSPEND#_11") (pintype "unspecified+no_connect"))
    )
    (net (code "62") (name "unconnected-(U1-SUSPEND-Pad12)") (class "Default")
      (node (ref "U1") (pin "12") (pinfunction "SUSPEND_12") (pintype "unspecified+no_connect"))
    )
    (net (code "63") (name "unconnected-(U3-IO13-Pad16)") (class "Default")
      (node (ref "U3") (pin "16") (pinfunction "IO13_16") (pintype "input"))
    )
    (net (code "64") (name "unconnected-(U3-IO14-Pad13)") (class "Default")
      (node (ref "U3") (pin "13") (pinfunction "IO14_13") (pintype "input"))
    )
    (net (code "65") (name "unconnected-(U3-IO16-Pad27)") (class "Default")
      (node (ref "U3") (pin "27") (pinfunction "IO16_27") (pintype "input"))
    )
    (net (code "66") (name "unconnected-(U3-IO17-Pad28)") (class "Default")
      (node (ref "U3") (pin "28") (pinfunction "IO17_28") (pintype "input"))
    )
    (net (code "67") (name "unconnected-(U3-IO25-Pad10)") (class "Default")
      (node (ref "U3") (pin "10") (pinfunction "IO25_10") (pintype "input"))
    )
    (net (code "68") (name "unconnected-(U3-IO26-Pad11)") (class "Default")
      (node (ref "U3") (pin "11") (pinfunction "IO26_11") (pintype "input"))
    )
    (net (code "69") (name "unconnected-(U3-IO27-Pad12)") (class "Default")
      (node (ref "U3") (pin "12") (pinfunction "IO27_12") (pintype "input"))
    )
    (net (code "70") (name "unconnected-(U3-IO32-Pad8)") (class "Default")
      (node (ref "U3") (pin "8") (pinfunction "IO32_8") (pintype "input"))
    )
    (net (code "71") (name "unconnected-(U3-IO33-Pad9)") (class "Default")
      (node (ref "U3") (pin "9") (pinfunction "IO33_9") (pintype "input"))
    )
    (net (code "72") (name "unconnected-(U3-IO34-Pad6)") (class "Default")
      (node (ref "U3") (pin "6") (pinfunction "IO34_6") (pintype "input"))
    )
    (net (code "73") (name "unconnected-(U3-IO35-Pad7)") (class "Default")
      (node (ref "U3") (pin "7") (pinfunction "IO35_7") (pintype "input"))
    )
    (net (code "74") (name "unconnected-(U3-NC-Pad32)") (class "Default")
      (node (ref "U3") (pin "32") (pinfunction "NC_32") (pintype "input+no_connect"))
    )
    (net (code "75") (name "unconnected-(U3-SCK{slash}CLK-Pad20)") (class "Default")
      (node (ref "U3") (pin "20") (pinfunction "SCK/CLK_20") (pintype "input"))
    )
    (net (code "76") (name "unconnected-(U3-SCS{slash}CMD-Pad19)") (class "Default")
      (node (ref "U3") (pin "19") (pinfunction "SCS/CMD_19") (pintype "input"))
    )
    (net (code "77") (name "unconnected-(U3-SDI{slash}SD1-Pad22)") (class "Default")
      (node (ref "U3") (pin "22") (pinfunction "SDI/SD1_22") (pintype "input"))
    )
    (net (code "78") (name "unconnected-(U3-SDO{slash}SD0-Pad21)") (class "Default")
      (node (ref "U3") (pin "21") (pinfunction "SDO/SD0_21") (pintype "input"))
    )
    (net (code "79") (name "unconnected-(U3-SENSOR_VN-Pad5)") (class "Default")
      (node (ref "U3") (pin "5") (pinfunction "SENSOR_VN_5") (pintype "input"))
    )
    (net (code "80") (name "unconnected-(U3-SENSOR_VP-Pad4)") (class "Default")
      (node (ref "U3") (pin "4") (pinfunction "SENSOR_VP_4") (pintype "input"))
    )
    (net (code "81") (name "unconnected-(U3-SHD{slash}SD2-Pad17)") (class "Default")
      (node (ref "U3") (pin "17") (pinfunction "SHD/SD2_17") (pintype "input"))
    )
    (net (code "82") (name "unconnected-(U3-SWP{slash}SD3-Pad18)") (class "Default")
      (node (ref "U3") (pin "18") (pinfunction "SWP/SD3_18") (pintype "input"))
    )
    (net (code "83") (name "unconnected-(USBC1-GND-PadA12)") (class "Default")
      (node (ref "USBC1") (pin "A12") (pinfunction "GND_A12") (pintype "unspecified+no_connect"))
    )
    (net (code "84") (name "unconnected-(USBC1-GND-PadB12)") (class "Default")
      (node (ref "USBC1") (pin "B12") (pinfunction "GND_B12") (pintype "unspecified+no_connect"))
    )
    (net (code "85") (name "unconnected-(USBC1-SBU1-PadA8)") (class "Default")
      (node (ref "USBC1") (pin "A8") (pinfunction "SBU1_A8") (pintype "unspecified+no_connect"))
    )
    (net (code "86") (name "unconnected-(USBC1-SBU2-PadB8)") (class "Default")
      (node (ref "USBC1") (pin "B8") (pinfunction "SBU2_B8") (pintype "unspecified"))
    )
  )
)
